# Power.net
KiCad netlist of a schematic drawn in Altium Designer
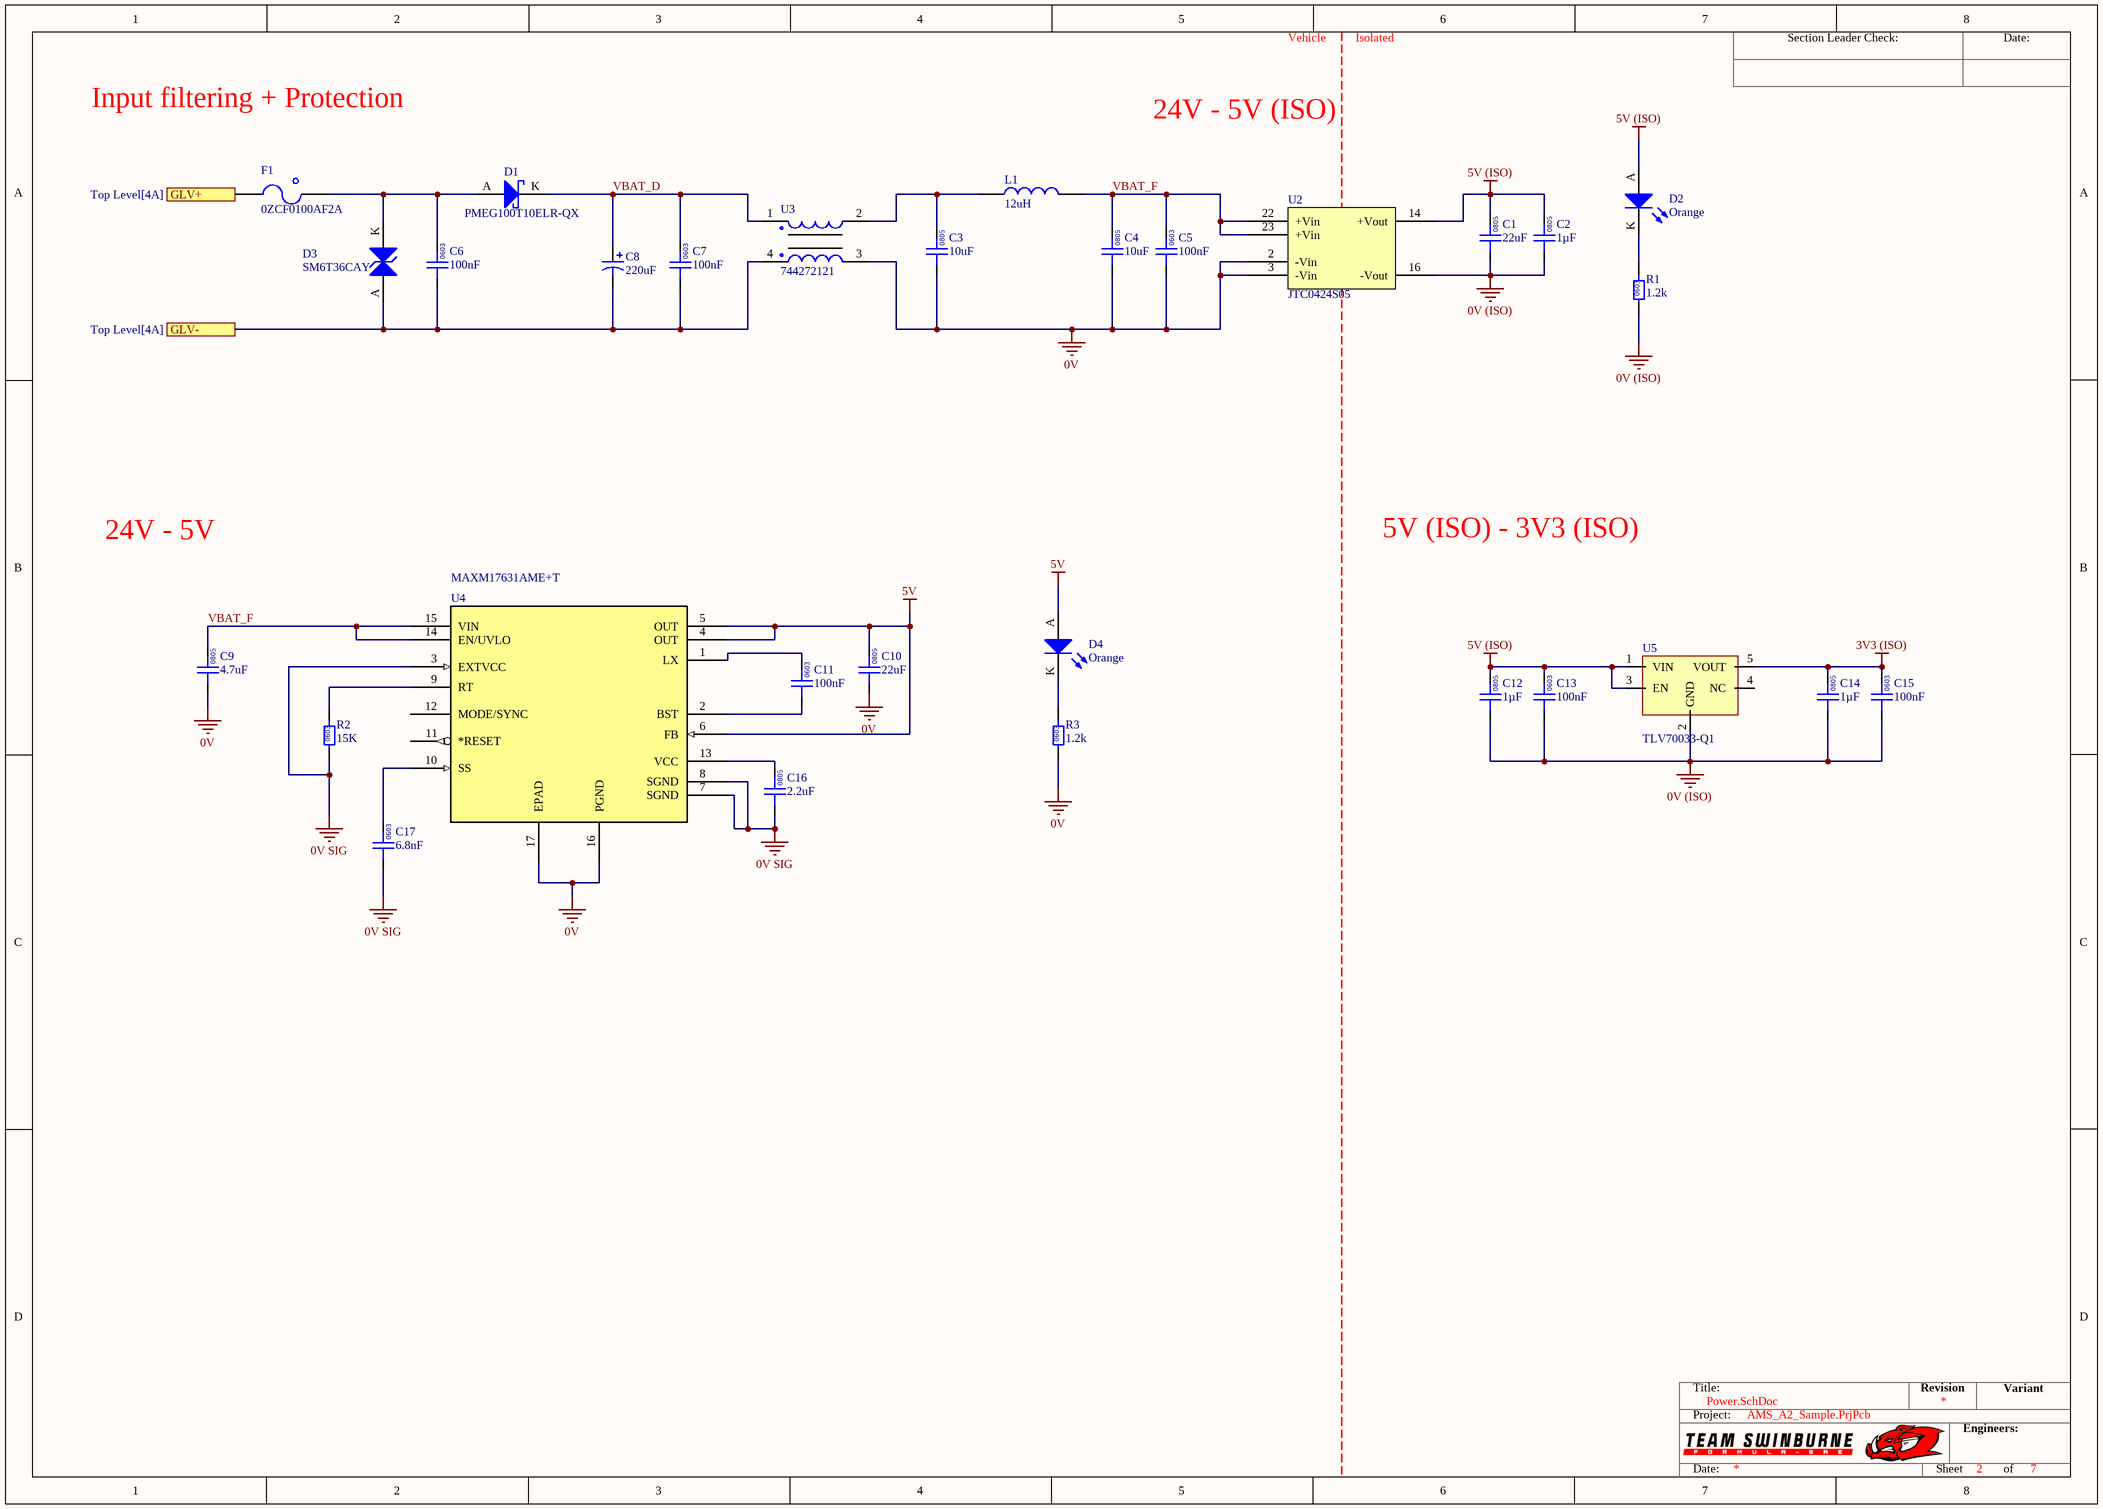
[diagram p0: Power.SchDoc]

(export (version "E")
  (design (tool "Eeschema 10.0.6"))
  (components
    (comp (ref "C1")
      (value "22uF")
      (footprint "0805")
      (fields
        (field (name "PART NUMBER") "GRM21BR61A226ME51L")
        (field (name "MANUFACTURER") "muRata")
        (field (name "TOLERANCE") "20%")
      )
      (libsource (lib "ts_standard_library") (part "Capacitor 0805"))
    )
    (comp (ref "C2")
      (value "1µF")
      (footprint "0805")
      (fields
        (field (name "PART NUMBER") "GCM21BR71H105KA03L")
        (field (name "MANUFACTURER") "muRata")
        (field (name "TOLERANCE") "±10%")
      )
      (libsource (lib "ts_standard_library") (part "Capacitor 0805"))
    )
    (comp (ref "C3")
      (value "10uF")
      (footprint "0805")
      (fields
        (field (name "PART NUMBER") "GRM21BR6YA106KE43L")
        (field (name "MANUFACTURER") "muRata")
        (field (name "TOLERANCE") "10%")
      )
      (libsource (lib "ts_standard_library") (part "Capacitor 0805"))
    )
    (comp (ref "C4")
      (value "10uF")
      (footprint "0805")
      (fields
        (field (name "PART NUMBER") "GRM21BR6YA106KE43L")
        (field (name "MANUFACTURER") "muRata")
        (field (name "TOLERANCE") "10%")
      )
      (libsource (lib "ts_standard_library") (part "Capacitor 0805"))
    )
    (comp (ref "C5")
      (value "100nF")
      (footprint "0603")
      (fields
        (field (name "PART NUMBER") "GCM188L81H104KA57D")
        (field (name "MANUFACTURER") "muRata")
        (field (name "TOLERANCE") "±10%")
      )
      (libsource (lib "ts_standard_library") (part "Capacitor 0603"))
    )
    (comp (ref "C6")
      (value "100nF")
      (footprint "0603")
      (fields
        (field (name "PART NUMBER") "GCM188L81H104KA57D")
        (field (name "MANUFACTURER") "muRata")
        (field (name "TOLERANCE") "±10%")
      )
      (libsource (lib "ts_standard_library") (part "Capacitor 0603"))
    )
    (comp (ref "C7")
      (value "100nF")
      (footprint "0603")
      (fields
        (field (name "PART NUMBER") "GCM188L81H104KA57D")
        (field (name "MANUFACTURER") "muRata")
        (field (name "TOLERANCE") "±10%")
      )
      (libsource (lib "ts_standard_library") (part "Capacitor 0603"))
    )
    (comp (ref "C8")
      (value "~")
      (footprint "Vishay Radial 1213")
      (fields
        (field (name "PART NUMBER") "MAL214699106E3")
        (field (name "MANUFACTURER") "Vishay")
        (field (name "TOLERANCE") "20%")
      )
      (libsource (lib "ts_standard_library") (part "Capacitor (Polarised)"))
    )
    (comp (ref "C9")
      (value "4.7uF")
      (footprint "0805")
      (fields
        (field (name "PART NUMBER") "GRM21BR71E225KE11L")
        (field (name "MANUFACTURER") "Murata Electronics")
        (field (name "TOLERANCE") "±10%")
      )
      (libsource (lib "ts_standard_library") (part "Capacitor 0805"))
    )
    (comp (ref "C10")
      (value "22uF")
      (footprint "0805")
      (fields
        (field (name "PART NUMBER") "GRM21BR61A226ME51L")
        (field (name "MANUFACTURER") "muRata")
        (field (name "TOLERANCE") "20%")
      )
      (libsource (lib "ts_standard_library") (part "Capacitor 0805"))
    )
    (comp (ref "C11")
      (value "100nF")
      (footprint "0603")
      (fields
        (field (name "PART NUMBER") "GCM188L81H104KA57D")
        (field (name "MANUFACTURER") "muRata")
        (field (name "TOLERANCE") "±10%")
      )
      (libsource (lib "ts_standard_library") (part "Capacitor 0603"))
    )
    (comp (ref "C12")
      (value "1µF")
      (footprint "0805")
      (fields
        (field (name "PART NUMBER") "GCM21BR71H105KA03L")
        (field (name "MANUFACTURER") "muRata")
        (field (name "TOLERANCE") "±10%")
      )
      (libsource (lib "ts_standard_library") (part "Capacitor 0805"))
    )
    (comp (ref "C13")
      (value "100nF")
      (footprint "0603")
      (fields
        (field (name "PART NUMBER") "GCM188L81H104KA57D")
        (field (name "MANUFACTURER") "muRata")
        (field (name "TOLERANCE") "±10%")
      )
      (libsource (lib "ts_standard_library") (part "Capacitor 0603"))
    )
    (comp (ref "C14")
      (value "1µF")
      (footprint "0805")
      (fields
        (field (name "PART NUMBER") "GCM21BR71H105KA03L")
        (field (name "MANUFACTURER") "muRata")
        (field (name "TOLERANCE") "±10%")
      )
      (libsource (lib "ts_standard_library") (part "Capacitor 0805"))
    )
    (comp (ref "C15")
      (value "100nF")
      (footprint "0603")
      (fields
        (field (name "PART NUMBER") "GCM188L81H104KA57D")
        (field (name "MANUFACTURER") "muRata")
        (field (name "TOLERANCE") "±10%")
      )
      (libsource (lib "ts_standard_library") (part "Capacitor 0603"))
    )
    (comp (ref "C16")
      (value "2.2uF")
      (footprint "0805")
      (fields
        (field (name "PART NUMBER") "GRM21BR71E225KE11L")
        (field (name "MANUFACTURER") "Murata Electronics")
        (field (name "TOLERANCE") "±10%")
      )
      (libsource (lib "ts_standard_library") (part "Capacitor 0805"))
    )
    (comp (ref "C17")
      (value "6.8nF")
      (footprint "0603")
      (fields
        (field (name "PART NUMBER") "GRM1885C1H682JA01D")
        (field (name "MANUFACTURER") "Murata Electronics")
        (field (name "TOLERANCE") "±5%")
      )
      (libsource (lib "ts_standard_library") (part "Capacitor 0603"))
    )
    (comp (ref "D1")
      (value "PMEG100T10ELR-QX")
      (footprint "NXP SOD123W")
      (fields
        (field (name "MANUFACTURER") "Nexperia USA Inc.")
        (field (name "DIGIKEY PART NUMBER") "1727-PMEG100T10ELR-QXCT-ND")
      )
      (libsource (lib "ts_standard_library") (part "Diode (Schottky)"))
    )
    (comp (ref "D2")
      (value "Orange")
      (footprint "0805 LED")
      (description "Orange LED Indication - Discrete 1.75V 0805 (2012 Metric)")
      (fields (field (name "PART NUMBER") "SML-211DTT86") (field (name "MANUFACTURER") "ROHM Semiconductor"))
      (libsource (lib "ts_standard_library") (part "LED"))
    )
    (comp (ref "D3")
      (value "SM6T36CAY")
      (footprint "ST SMB DIODE")
      (fields
        (field (name "MANUFACTURER") "STMicroelectronics")
        (field (name "DIGIKEY PART NUMBER") "497-10804-1-ND")
      )
      (libsource (lib "ts_standard_library") (part "TVS (Bidirectional)"))
    )
    (comp (ref "D4")
      (value "Orange")
      (footprint "0805 LED")
      (description "Orange LED Indication - Discrete 1.75V 0805 (2012 Metric)")
      (fields (field (name "PART NUMBER") "SML-211DTT86") (field (name "MANUFACTURER") "ROHM Semiconductor"))
      (libsource (lib "ts_standard_library") (part "LED"))
    )
    (comp (ref "F1")
      (value "0ZCF0100AF2A")
      (footprint "2920")
      (description "PTC RESET FUSE 60V 1A 292")
      (fields
        (field (name "MANUFACTURER") "Littelfuse Inc.")
        (field (name "DIGIKEY PART NUMBER") "507-2070-1-ND")
      )
      (libsource (lib "ts_standard_library") (part "PTC Fuse"))
    )
    (comp (ref "L1")
      (value "12uH")
      (footprint "1812")
      (fields
        (field (name "PART NUMBER") "RLS-126")
        (field (name "MANUFACTURER") "Recom")
        (field (name "TOLERANCE") "0.2")
      )
      (libsource (lib "ts_standard_library") (part "Inductor"))
    )
    (comp (ref "R1")
      (value "1.2k")
      (footprint "0603")
      (fields
        (field (name "PART NUMBER") "RC0603JR-071K2L")
        (field (name "MANUFACTURER") "YAGEO")
        (field (name "TOLERANCE") "0.01")
      )
      (libsource (lib "ts_standard_library") (part "Resistor 0603"))
    )
    (comp (ref "R2")
      (value "15K")
      (footprint "0603")
      (fields
        (field (name "PART NUMBER") "ESR03EZPF1502")
        (field (name "MANUFACTURER") "Rohm Semiconductor")
        (field (name "TOLERANCE") "0.01")
      )
      (libsource (lib "ts_standard_library") (part "Resistor 0603"))
    )
    (comp (ref "R3")
      (value "1.2k")
      (footprint "0603")
      (fields
        (field (name "PART NUMBER") "RC0603JR-071K2L")
        (field (name "MANUFACTURER") "YAGEO")
        (field (name "TOLERANCE") "0.01")
      )
      (libsource (lib "ts_standard_library") (part "Resistor 0603"))
    )
    (comp (ref "U2")
      (value "JTC0424S05")
      (footprint "24-DIP Module, 7 Leads")
      (description "DC DC CONVERTER 5V 4W")
      (fields (field (name "MANUFACTURER") "XP Power") (field (name "DIGIKEY PART NUMBER") "JTC0424S05-ND"))
      (libsource (lib "ts_20-standard-library") (part "JTC0424S05"))
    )
    (comp (ref "U3")
      (value "744272121")
      (footprint "Wurth 4-PC Pad")
      (fields
        (field (name "MANUFACTURER") "Wurth Electronics Inc")
        (field (name "DIGIKEY PART NUMBER") "732-1489-1-ND")
      )
      (libsource (lib "ts_standard_library") (part "CM Choke"))
    )
    (comp (ref "U4")
      (value "MAXM17631AME+T")
      (footprint "MAXM17631AME+T")
      (description "DC DC CONVERTER 5V")
      (fields
        (field (name "MANUFACTURER") "Analog Devices")
        (field (name "DIGIKEY PART NUMBER") "175-MAXM17631AME+TTR-ND")
      )
      (libsource (lib "ts_standard_library") (part "MAXM17631AME+T"))
    )
    (comp (ref "U5")
      (value "TLV70033-Q1")
      (footprint "TI SOT-23-5")
      (description "IC REG LINEAR 3.3V 200MA SOT23-5")
      (fields
        (field (name "MANUFACTURER") "Texas Instruments")
        (field (name "DIGIKEY PART NUMBER") "296-27780-1-ND")
      )
      (libsource (lib "ts_standard_library") (part "TLV70033-Q1"))
    )
  )
  (nets
    (net (code "1") (name "/GLV+") (class "Default")
      (node (ref "F1") (pin "1") (pinfunction "1_1") (pintype "passive"))
    )
    (net (code "2") (name "/GLV-") (class "Default")
      (node (ref "C6") (pin "1") (pinfunction "1_1") (pintype "passive"))
      (node (ref "C7") (pin "1") (pinfunction "1_1") (pintype "passive"))
      (node (ref "C8") (pin "1") (pinfunction "1_1") (pintype "passive"))
      (node (ref "D3") (pin "A") (pinfunction "A_A") (pintype "passive"))
      (node (ref "U3") (pin "4") (pinfunction "4_4") (pintype "passive"))
    )
    (net (code "3") (name "/VBAT_D") (class "Default")
      (node (ref "C7") (pin "2") (pinfunction "2_2") (pintype "passive"))
      (node (ref "C8") (pin "2") (pinfunction "2_2") (pintype "passive"))
      (node (ref "D1") (pin "K") (pinfunction "K_K") (pintype "passive"))
      (node (ref "U3") (pin "1") (pinfunction "1_1") (pintype "passive"))
    )
    (net (code "4") (name "/VBAT_F") (class "Default")
      (node (ref "C4") (pin "2") (pinfunction "2_2") (pintype "passive"))
      (node (ref "C5") (pin "2") (pinfunction "2_2") (pintype "passive"))
      (node (ref "C9") (pin "2") (pinfunction "2_2") (pintype "passive"))
      (node (ref "L1") (pin "1") (pinfunction "1_1") (pintype "passive"))
      (node (ref "U2") (pin "22") (pinfunction "+Vin_22") (pintype "passive"))
      (node (ref "U2") (pin "23") (pinfunction "+Vin_23") (pintype "passive"))
      (node (ref "U4") (pin "14") (pinfunction "EN/UVLO_14") (pintype "passive"))
      (node (ref "U4") (pin "15") (pinfunction "VIN_15") (pintype "power_in"))
    )
    (net (code "5") (name "0V") (class "Default")
      (node (ref "C10") (pin "1") (pinfunction "1_1") (pintype "passive"))
      (node (ref "C3") (pin "1") (pinfunction "1_1") (pintype "passive"))
      (node (ref "C4") (pin "1") (pinfunction "1_1") (pintype "passive"))
      (node (ref "C5") (pin "1") (pinfunction "1_1") (pintype "passive"))
      (node (ref "C9") (pin "1") (pinfunction "1_1") (pintype "passive"))
      (node (ref "R3") (pin "1") (pinfunction "1_1") (pintype "passive"))
      (node (ref "U2") (pin "2") (pinfunction "-Vin_2") (pintype "passive"))
      (node (ref "U2") (pin "3") (pinfunction "-Vin_3") (pintype "passive"))
      (node (ref "U3") (pin "3") (pinfunction "3_3") (pintype "power_in"))
      (node (ref "U4") (pin "16") (pinfunction "PGND_16") (pintype "power_in"))
      (node (ref "U4") (pin "17") (pinfunction "EPAD_17") (pintype "power_in"))
    )
    (net (code "6") (name "0V (ISO)") (class "Default")
      (node (ref "C1") (pin "1") (pinfunction "1_1") (pintype "passive"))
      (node (ref "C12") (pin "1") (pinfunction "1_1") (pintype "passive"))
      (node (ref "C13") (pin "1") (pinfunction "1_1") (pintype "passive"))
      (node (ref "C14") (pin "1") (pinfunction "1_1") (pintype "passive"))
      (node (ref "C15") (pin "1") (pinfunction "1_1") (pintype "passive"))
      (node (ref "C2") (pin "1") (pinfunction "1_1") (pintype "passive"))
      (node (ref "R1") (pin "1") (pinfunction "1_1") (pintype "passive"))
      (node (ref "U2") (pin "16") (pinfunction "-Vout_16") (pintype "passive"))
      (node (ref "U5") (pin "2") (pinfunction "GND_2") (pintype "passive"))
    )
    (net (code "7") (name "0V SIG") (class "Default")
      (node (ref "C16") (pin "1") (pinfunction "1_1") (pintype "passive"))
      (node (ref "C17") (pin "1") (pinfunction "1_1") (pintype "passive"))
      (node (ref "R2") (pin "1") (pinfunction "1_1") (pintype "passive"))
      (node (ref "U4") (pin "3") (pinfunction "EXTVCC_3") (pintype "input"))
      (node (ref "U4") (pin "7") (pinfunction "SGND_7") (pintype "power_in"))
      (node (ref "U4") (pin "8") (pinfunction "SGND_8") (pintype "power_in"))
    )
    (net (code "8") (name "3V3 (ISO)") (class "Default")
      (node (ref "C14") (pin "2") (pinfunction "2_2") (pintype "passive"))
      (node (ref "C15") (pin "2") (pinfunction "2_2") (pintype "passive"))
      (node (ref "U5") (pin "5") (pinfunction "VOUT_5") (pintype "passive"))
    )
    (net (code "9") (name "5V") (class "Default")
      (node (ref "C10") (pin "2") (pinfunction "2_2") (pintype "passive"))
      (node (ref "D4") (pin "A") (pinfunction "A_A") (pintype "passive"))
      (node (ref "U4") (pin "4") (pinfunction "OUT_4") (pintype "power_in"))
      (node (ref "U4") (pin "5") (pinfunction "OUT_5") (pintype "power_in"))
      (node (ref "U4") (pin "6") (pinfunction "FB_6") (pintype "input"))
    )
    (net (code "10") (name "5V (ISO)") (class "Default")
      (node (ref "C1") (pin "2") (pinfunction "2_2") (pintype "passive"))
      (node (ref "C12") (pin "2") (pinfunction "2_2") (pintype "passive"))
      (node (ref "C13") (pin "2") (pinfunction "2_2") (pintype "passive"))
      (node (ref "C2") (pin "2") (pinfunction "2_2") (pintype "passive"))
      (node (ref "D2") (pin "A") (pinfunction "A_A") (pintype "passive"))
      (node (ref "U2") (pin "14") (pinfunction "+Vout_14") (pintype "passive"))
      (node (ref "U5") (pin "1") (pinfunction "VIN_1") (pintype "passive"))
      (node (ref "U5") (pin "3") (pinfunction "EN_3") (pintype "passive"))
    )
    (net (code "11") (name "Net-(C3-Pad2)") (class "Default")
      (node (ref "C3") (pin "2") (pinfunction "2_2") (pintype "passive"))
      (node (ref "L1") (pin "2") (pinfunction "2_2") (pintype "passive"))
      (node (ref "U3") (pin "2") (pinfunction "2_2") (pintype "passive"))
    )
    (net (code "12") (name "Net-(C6-Pad2)") (class "Default")
      (node (ref "C6") (pin "2") (pinfunction "2_2") (pintype "passive"))
      (node (ref "D1") (pin "A") (pinfunction "A_A") (pintype "passive"))
      (node (ref "D3") (pin "K") (pinfunction "K_K") (pintype "passive"))
      (node (ref "F1") (pin "2") (pinfunction "2_2") (pintype "passive"))
    )
    (net (code "13") (name "Net-(D2-PadK)") (class "Default")
      (node (ref "D2") (pin "K") (pinfunction "K_K") (pintype "passive"))
      (node (ref "R1") (pin "2") (pinfunction "2_2") (pintype "passive"))
    )
    (net (code "14") (name "Net-(D4-PadK)") (class "Default")
      (node (ref "D4") (pin "K") (pinfunction "K_K") (pintype "passive"))
      (node (ref "R3") (pin "2") (pinfunction "2_2") (pintype "passive"))
    )
    (net (code "15") (name "Net-(U4-BST)") (class "Default")
      (node (ref "C11") (pin "1") (pinfunction "1_1") (pintype "passive"))
      (node (ref "U4") (pin "2") (pinfunction "BST_2") (pintype "passive"))
    )
    (net (code "16") (name "Net-(U4-LX)") (class "Default")
      (node (ref "C11") (pin "2") (pinfunction "2_2") (pintype "passive"))
      (node (ref "U4") (pin "1") (pinfunction "LX_1") (pintype "passive"))
    )
    (net (code "17") (name "Net-(U4-RT)") (class "Default")
      (node (ref "R2") (pin "2") (pinfunction "2_2") (pintype "passive"))
      (node (ref "U4") (pin "9") (pinfunction "RT_9") (pintype "passive"))
    )
    (net (code "18") (name "Net-(U4-SS)") (class "Default")
      (node (ref "C17") (pin "2") (pinfunction "2_2") (pintype "passive"))
      (node (ref "U4") (pin "10") (pinfunction "SS_10") (pintype "input"))
    )
    (net (code "19") (name "Net-(U4-VCC)") (class "Default")
      (node (ref "C16") (pin "2") (pinfunction "2_2") (pintype "passive"))
      (node (ref "U4") (pin "13") (pinfunction "VCC_13") (pintype "power_in"))
    )
    (net (code "20") (name "unconnected-(U4-*RESET-Pad11)") (class "Default")
      (node (ref "U4") (pin "11") (pinfunction "*RESET_11") (pintype "output"))
    )
    (net (code "21") (name "unconnected-(U4-MODE{slash}SYNC-Pad12)") (class "Default")
      (node (ref "U4") (pin "12") (pinfunction "MODE/SYNC_12") (pintype "passive"))
    )
    (net (code "22") (name "unconnected-(U5-NC-Pad4)") (class "Default")
      (node (ref "U5") (pin "4") (pinfunction "NC_4") (pintype "passive"))
    )
  )
)
